# Sheet2.net
KiCad netlist of a schematic drawn in Altium Designer
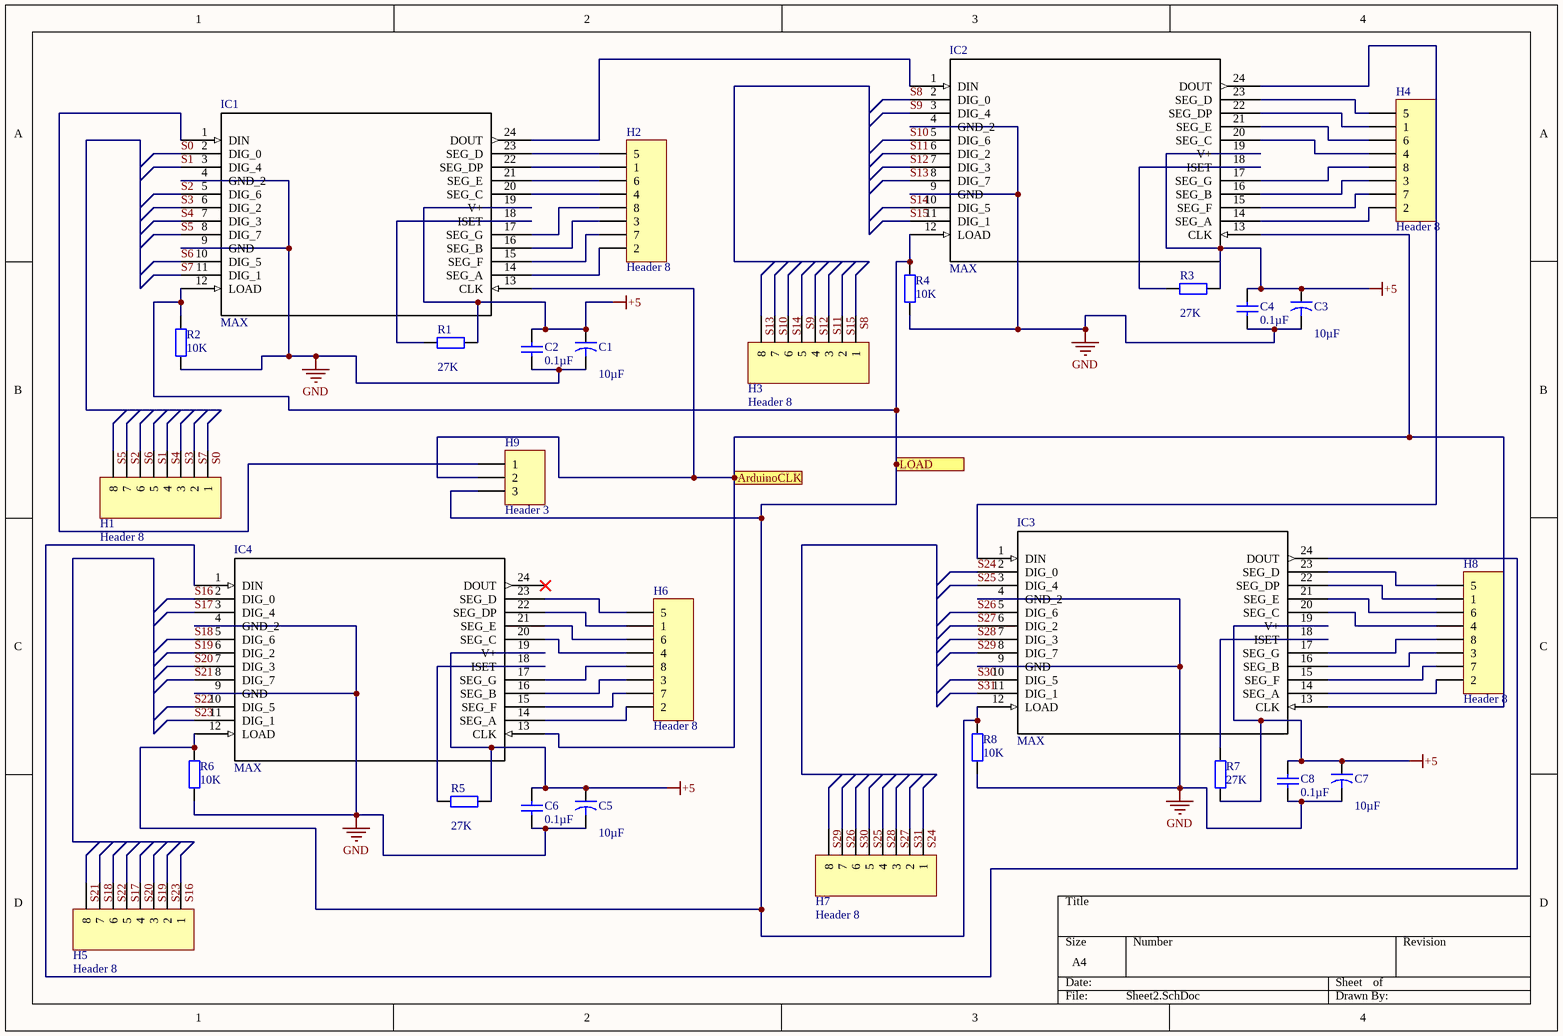
[diagram p0: Sheet2.SchDoc]

(export (version "E")
  (design (tool "Eeschema 10.0.6"))
  (components
    (comp (ref "C1")
      (value "10µF")
      (footprint "CAPR5-4X5")
      (description "Capacitor")
      (fields (field (name "Comment") "Cap2") (field (name "PUBLISHER") "Altium Limited"))
      (libsource (lib "Miscellaneous Devices") (part "Cap2"))
    )
    (comp (ref "C2")
      (value "0.1µF")
      (footprint "CAPC2013X94X50ML20T25")
      (description "Chip Capacitor, Ceramic, 0.1 uF, 10%, 50 V, 0805, RoHS, Tape and Reel")
      (fields (field (name "MANUFACTURER") "AVX"))
      (libsource (lib "Altium Content Vault") (part "CAP-NP-2"))
    )
    (comp (ref "C3")
      (value "10µF")
      (footprint "CAPR5-4X5")
      (description "Capacitor")
      (fields (field (name "Comment") "Cap2") (field (name "PUBLISHER") "Altium Limited"))
      (libsource (lib "Miscellaneous Devices") (part "Cap2"))
    )
    (comp (ref "C4")
      (value "0.1µF")
      (footprint "CAPC2013X94X50ML20T25")
      (description "Chip Capacitor, Ceramic, 0.1 uF, 10%, 50 V, 0805, RoHS, Tape and Reel")
      (fields (field (name "MANUFACTURER") "AVX"))
      (libsource (lib "Altium Content Vault") (part "CAP-NP-2"))
    )
    (comp (ref "C5")
      (value "10µF")
      (footprint "CAPR5-4X5")
      (description "Capacitor")
      (fields (field (name "Comment") "Cap2") (field (name "PUBLISHER") "Altium Limited"))
      (libsource (lib "Miscellaneous Devices") (part "Cap2"))
    )
    (comp (ref "C6")
      (value "0.1µF")
      (footprint "CAPC2013X94X50ML20T25")
      (description "Chip Capacitor, Ceramic, 0.1 uF, 10%, 50 V, 0805, RoHS, Tape and Reel")
      (fields (field (name "MANUFACTURER") "AVX"))
      (libsource (lib "Altium Content Vault") (part "CAP-NP-2"))
    )
    (comp (ref "C7")
      (value "10µF")
      (footprint "CAPR5-4X5")
      (description "Capacitor")
      (fields (field (name "Comment") "Cap2") (field (name "PUBLISHER") "Altium Limited"))
      (libsource (lib "Miscellaneous Devices") (part "Cap2"))
    )
    (comp (ref "C8")
      (value "0.1µF")
      (footprint "CAPC2013X94X50ML20T25")
      (description "Chip Capacitor, Ceramic, 0.1 uF, 10%, 50 V, 0805, RoHS, Tape and Reel")
      (fields (field (name "MANUFACTURER") "AVX"))
      (libsource (lib "Altium Content Vault") (part "CAP-NP-2"))
    )
    (comp (ref "H1")
      (value "Header 8")
      (footprint "HDR1X8")
      (description "Header, 8-Pin")
      (fields (field (name "PUBLISHER") "Altium Limited"))
      (libsource (lib "Miscellaneous Connectors") (part "Header 8"))
    )
    (comp (ref "H2")
      (value "Header 8")
      (footprint "HDR1X8")
      (description "Header, 8-Pin")
      (fields (field (name "PUBLISHER") "Altium Limited"))
      (libsource (lib "PCB_Project_1") (part "Header 8"))
    )
    (comp (ref "H3")
      (value "Header 8")
      (footprint "HDR1X8")
      (description "Header, 8-Pin")
      (fields (field (name "PUBLISHER") "Altium Limited"))
      (libsource (lib "Miscellaneous Connectors") (part "Header 8"))
    )
    (comp (ref "H4")
      (value "Header 8")
      (footprint "HDR1X8")
      (description "Header, 8-Pin")
      (fields (field (name "PUBLISHER") "Altium Limited"))
      (libsource (lib "PCB_Project_1") (part "Header 8"))
    )
    (comp (ref "H5")
      (value "Header 8")
      (footprint "HDR1X8")
      (description "Header, 8-Pin")
      (fields (field (name "PUBLISHER") "Altium Limited"))
      (libsource (lib "Miscellaneous Connectors") (part "Header 8"))
    )
    (comp (ref "H6")
      (value "Header 8")
      (footprint "HDR1X8")
      (description "Header, 8-Pin")
      (fields (field (name "PUBLISHER") "Altium Limited"))
      (libsource (lib "PCB_Project_1") (part "Header 8"))
    )
    (comp (ref "H7")
      (value "Header 8")
      (footprint "HDR1X8")
      (description "Header, 8-Pin")
      (fields (field (name "PUBLISHER") "Altium Limited"))
      (libsource (lib "Miscellaneous Connectors") (part "Header 8"))
    )
    (comp (ref "H8")
      (value "Header 8")
      (footprint "HDR1X8")
      (description "Header, 8-Pin")
      (fields (field (name "PUBLISHER") "Altium Limited"))
      (libsource (lib "PCB_Project_1") (part "Header 8"))
    )
    (comp (ref "H9")
      (value "Header 3")
      (footprint "HDR1X3")
      (description "Header, 3-Pin")
      (fields (field (name "PUBLISHER") "Altium Limited"))
      (libsource (lib "Miscellaneous Connectors") (part "Header 3"))
    )
    (comp (ref "IC1")
      (value "MAX")
      (footprint "MAX7219CWGT:*21-0042B_24")
      (libsource (lib "PCB_Project_1") (part "MAX"))
    )
    (comp (ref "IC2") (value "MAX") (footprint "*21-0042B_24") (libsource (lib "PCB_Project_1") (part "MAX")))
    (comp (ref "IC3") (value "MAX") (footprint "*21-0042B_24") (libsource (lib "PCB_Project_1") (part "MAX")))
    (comp (ref "IC4") (value "MAX") (footprint "*21-0042B_24") (libsource (lib "PCB_Project_1") (part "MAX")))
    (comp (ref "R1")
      (value "27K")
      (footprint "AXIAL-0.4")
      (description "Resistor")
      (fields (field (name "Comment") "Res2") (field (name "PUBLISHER") "Altium Limited"))
      (libsource (lib "") (part "Res2_1"))
    )
    (comp (ref "R2")
      (value "10K")
      (footprint "AXIAL-0.4")
      (description "Resistor")
      (fields (field (name "Comment") "Res2") (field (name "PUBLISHER") "Altium Limited"))
      (libsource (lib "Miscellaneous Devices") (part "Res2"))
    )
    (comp (ref "R3")
      (value "27K")
      (footprint "AXIAL-0.4")
      (description "Resistor")
      (fields (field (name "Comment") "Res2") (field (name "PUBLISHER") "Altium Limited"))
      (libsource (lib "") (part "Res2_1"))
    )
    (comp (ref "R4")
      (value "10K")
      (footprint "AXIAL-0.4")
      (description "Resistor")
      (fields (field (name "Comment") "Res2") (field (name "PUBLISHER") "Altium Limited"))
      (libsource (lib "Miscellaneous Devices") (part "Res2"))
    )
    (comp (ref "R5")
      (value "27K")
      (footprint "AXIAL-0.4")
      (description "Resistor")
      (fields (field (name "Comment") "Res2") (field (name "PUBLISHER") "Altium Limited"))
      (libsource (lib "") (part "Res2_1"))
    )
    (comp (ref "R6")
      (value "10K")
      (footprint "AXIAL-0.4")
      (description "Resistor")
      (fields (field (name "Comment") "Res2") (field (name "PUBLISHER") "Altium Limited"))
      (libsource (lib "Miscellaneous Devices") (part "Res2"))
    )
    (comp (ref "R7")
      (value "27K")
      (footprint "AXIAL-0.4")
      (description "Resistor")
      (fields (field (name "Comment") "Res2") (field (name "PUBLISHER") "Altium Limited"))
      (libsource (lib "Miscellaneous Devices") (part "Res2"))
    )
    (comp (ref "R8")
      (value "10K")
      (footprint "AXIAL-0.4")
      (description "Resistor")
      (fields (field (name "Comment") "Res2") (field (name "PUBLISHER") "Altium Limited"))
      (libsource (lib "Miscellaneous Devices") (part "Res2"))
    )
  )
  (nets
    (net (code "1") (name "+5") (class "Default")
      (node (ref "C1") (pin "1") (pinfunction "1_1") (pintype "passive"))
      (node (ref "C2") (pin "1") (pinfunction "1_1") (pintype "passive"))
      (node (ref "C3") (pin "1") (pinfunction "1_1") (pintype "passive"))
      (node (ref "C4") (pin "2") (pinfunction "2_2") (pintype "passive"))
      (node (ref "C5") (pin "1") (pinfunction "1_1") (pintype "passive"))
      (node (ref "C6") (pin "2") (pinfunction "2_2") (pintype "passive"))
      (node (ref "C7") (pin "1") (pinfunction "1_1") (pintype "passive"))
      (node (ref "C8") (pin "2") (pinfunction "2_2") (pintype "passive"))
      (node (ref "IC1") (pin "19") (pinfunction "V+_19") (pintype "power_in"))
      (node (ref "IC2") (pin "19") (pinfunction "V+_19") (pintype "power_in"))
      (node (ref "IC3") (pin "19") (pinfunction "V+_19") (pintype "power_in"))
      (node (ref "IC4") (pin "19") (pinfunction "V+_19") (pintype "power_in"))
      (node (ref "R1") (pin "2") (pinfunction "2_2") (pintype "passive"))
      (node (ref "R3") (pin "2") (pinfunction "2_2") (pintype "passive"))
      (node (ref "R5") (pin "2") (pinfunction "2_2") (pintype "passive"))
      (node (ref "R7") (pin "1") (pinfunction "1_1") (pintype "passive"))
    )
    (net (code "2") (name "/ArduinoCLK") (class "Default")
      (node (ref "H9") (pin "2") (pinfunction "2_2") (pintype "passive"))
      (node (ref "IC1") (pin "13") (pinfunction "CLK_13") (pintype "input"))
      (node (ref "IC2") (pin "13") (pinfunction "CLK_13") (pintype "input"))
      (node (ref "IC3") (pin "13") (pinfunction "CLK_13") (pintype "input"))
      (node (ref "IC4") (pin "13") (pinfunction "CLK_13") (pintype "input"))
    )
    (net (code "3") (name "/LOAD") (class "Default")
      (node (ref "H9") (pin "3") (pinfunction "3_3") (pintype "passive"))
      (node (ref "IC1") (pin "12") (pinfunction "LOAD_12") (pintype "input"))
      (node (ref "IC2") (pin "12") (pinfunction "LOAD_12") (pintype "input"))
      (node (ref "IC3") (pin "12") (pinfunction "LOAD_12") (pintype "input"))
      (node (ref "IC4") (pin "12") (pinfunction "LOAD_12") (pintype "input"))
      (node (ref "R2") (pin "2") (pinfunction "2_2") (pintype "passive"))
      (node (ref "R4") (pin "2") (pinfunction "2_2") (pintype "passive"))
      (node (ref "R6") (pin "2") (pinfunction "2_2") (pintype "passive"))
      (node (ref "R8") (pin "2") (pinfunction "2_2") (pintype "passive"))
    )
    (net (code "4") (name "/S0") (class "Default")
      (node (ref "H1") (pin "1") (pinfunction "1_1") (pintype "passive"))
      (node (ref "IC1") (pin "2") (pinfunction "DIG_0_2") (pintype "passive"))
    )
    (net (code "5") (name "/S1") (class "Default")
      (node (ref "H1") (pin "5") (pinfunction "5_5") (pintype "passive"))
      (node (ref "IC1") (pin "3") (pinfunction "DIG_4_3") (pintype "passive"))
    )
    (net (code "6") (name "/S2") (class "Default")
      (node (ref "H1") (pin "7") (pinfunction "7_7") (pintype "passive"))
      (node (ref "IC1") (pin "5") (pinfunction "DIG_6_5") (pintype "passive"))
    )
    (net (code "7") (name "/S3") (class "Default")
      (node (ref "H1") (pin "3") (pinfunction "3_3") (pintype "passive"))
      (node (ref "IC1") (pin "6") (pinfunction "DIG_2_6") (pintype "passive"))
    )
    (net (code "8") (name "/S4") (class "Default")
      (node (ref "H1") (pin "4") (pinfunction "4_4") (pintype "passive"))
      (node (ref "IC1") (pin "7") (pinfunction "DIG_3_7") (pintype "passive"))
    )
    (net (code "9") (name "/S5") (class "Default")
      (node (ref "H1") (pin "8") (pinfunction "8_8") (pintype "passive"))
      (node (ref "IC1") (pin "8") (pinfunction "DIG_7_8") (pintype "passive"))
    )
    (net (code "10") (name "/S6") (class "Default")
      (node (ref "H1") (pin "6") (pinfunction "6_6") (pintype "passive"))
      (node (ref "IC1") (pin "10") (pinfunction "DIG_5_10") (pintype "passive"))
    )
    (net (code "11") (name "/S7") (class "Default")
      (node (ref "H1") (pin "2") (pinfunction "2_2") (pintype "passive"))
      (node (ref "IC1") (pin "11") (pinfunction "DIG_1_11") (pintype "passive"))
    )
    (net (code "12") (name "/S8") (class "Default")
      (node (ref "H3") (pin "1") (pinfunction "1_1") (pintype "passive"))
      (node (ref "IC2") (pin "2") (pinfunction "DIG_0_2") (pintype "passive"))
    )
    (net (code "13") (name "/S9") (class "Default")
      (node (ref "H3") (pin "5") (pinfunction "5_5") (pintype "passive"))
      (node (ref "IC2") (pin "3") (pinfunction "DIG_4_3") (pintype "passive"))
    )
    (net (code "14") (name "/S10") (class "Default")
      (node (ref "H3") (pin "7") (pinfunction "7_7") (pintype "passive"))
      (node (ref "IC2") (pin "5") (pinfunction "DIG_6_5") (pintype "passive"))
    )
    (net (code "15") (name "/S11") (class "Default")
      (node (ref "H3") (pin "3") (pinfunction "3_3") (pintype "passive"))
      (node (ref "IC2") (pin "6") (pinfunction "DIG_2_6") (pintype "passive"))
    )
    (net (code "16") (name "/S12") (class "Default")
      (node (ref "H3") (pin "4") (pinfunction "4_4") (pintype "passive"))
      (node (ref "IC2") (pin "7") (pinfunction "DIG_3_7") (pintype "passive"))
    )
    (net (code "17") (name "/S13") (class "Default")
      (node (ref "H3") (pin "8") (pinfunction "8_8") (pintype "passive"))
      (node (ref "IC2") (pin "8") (pinfunction "DIG_7_8") (pintype "passive"))
    )
    (net (code "18") (name "/S14") (class "Default")
      (node (ref "H3") (pin "6") (pinfunction "6_6") (pintype "passive"))
      (node (ref "IC2") (pin "10") (pinfunction "DIG_5_10") (pintype "passive"))
    )
    (net (code "19") (name "/S15") (class "Default")
      (node (ref "H3") (pin "2") (pinfunction "2_2") (pintype "passive"))
      (node (ref "IC2") (pin "11") (pinfunction "DIG_1_11") (pintype "passive"))
    )
    (net (code "20") (name "/S16") (class "Default")
      (node (ref "H5") (pin "1") (pinfunction "1_1") (pintype "passive"))
      (node (ref "IC4") (pin "2") (pinfunction "DIG_0_2") (pintype "passive"))
    )
    (net (code "21") (name "/S17") (class "Default")
      (node (ref "H5") (pin "5") (pinfunction "5_5") (pintype "passive"))
      (node (ref "IC4") (pin "3") (pinfunction "DIG_4_3") (pintype "passive"))
    )
    (net (code "22") (name "/S18") (class "Default")
      (node (ref "H5") (pin "7") (pinfunction "7_7") (pintype "passive"))
      (node (ref "IC4") (pin "5") (pinfunction "DIG_6_5") (pintype "passive"))
    )
    (net (code "23") (name "/S19") (class "Default")
      (node (ref "H5") (pin "3") (pinfunction "3_3") (pintype "passive"))
      (node (ref "IC4") (pin "6") (pinfunction "DIG_2_6") (pintype "passive"))
    )
    (net (code "24") (name "/S20") (class "Default")
      (node (ref "H5") (pin "4") (pinfunction "4_4") (pintype "passive"))
      (node (ref "IC4") (pin "7") (pinfunction "DIG_3_7") (pintype "passive"))
    )
    (net (code "25") (name "/S21") (class "Default")
      (node (ref "H5") (pin "8") (pinfunction "8_8") (pintype "passive"))
      (node (ref "IC4") (pin "8") (pinfunction "DIG_7_8") (pintype "passive"))
    )
    (net (code "26") (name "/S22") (class "Default")
      (node (ref "H5") (pin "6") (pinfunction "6_6") (pintype "passive"))
      (node (ref "IC4") (pin "10") (pinfunction "DIG_5_10") (pintype "passive"))
    )
    (net (code "27") (name "/S23") (class "Default")
      (node (ref "H5") (pin "2") (pinfunction "2_2") (pintype "passive"))
      (node (ref "IC4") (pin "11") (pinfunction "DIG_1_11") (pintype "passive"))
    )
    (net (code "28") (name "/S24") (class "Default")
      (node (ref "H7") (pin "1") (pinfunction "1_1") (pintype "passive"))
      (node (ref "IC3") (pin "2") (pinfunction "DIG_0_2") (pintype "passive"))
    )
    (net (code "29") (name "/S25") (class "Default")
      (node (ref "H7") (pin "5") (pinfunction "5_5") (pintype "passive"))
      (node (ref "IC3") (pin "3") (pinfunction "DIG_4_3") (pintype "passive"))
    )
    (net (code "30") (name "/S26") (class "Default")
      (node (ref "H7") (pin "7") (pinfunction "7_7") (pintype "passive"))
      (node (ref "IC3") (pin "5") (pinfunction "DIG_6_5") (pintype "passive"))
    )
    (net (code "31") (name "/S27") (class "Default")
      (node (ref "H7") (pin "3") (pinfunction "3_3") (pintype "passive"))
      (node (ref "IC3") (pin "6") (pinfunction "DIG_2_6") (pintype "passive"))
    )
    (net (code "32") (name "/S28") (class "Default")
      (node (ref "H7") (pin "4") (pinfunction "4_4") (pintype "passive"))
      (node (ref "IC3") (pin "7") (pinfunction "DIG_3_7") (pintype "passive"))
    )
    (net (code "33") (name "/S29") (class "Default")
      (node (ref "H7") (pin "8") (pinfunction "8_8") (pintype "passive"))
      (node (ref "IC3") (pin "8") (pinfunction "DIG_7_8") (pintype "passive"))
    )
    (net (code "34") (name "/S30") (class "Default")
      (node (ref "H7") (pin "6") (pinfunction "6_6") (pintype "passive"))
      (node (ref "IC3") (pin "10") (pinfunction "DIG_5_10") (pintype "passive"))
    )
    (net (code "35") (name "/S31") (class "Default")
      (node (ref "H7") (pin "2") (pinfunction "2_2") (pintype "passive"))
      (node (ref "IC3") (pin "11") (pinfunction "DIG_1_11") (pintype "passive"))
    )
    (net (code "36") (name "GND") (class "Default")
      (node (ref "C1") (pin "2") (pinfunction "2_2") (pintype "passive"))
      (node (ref "C2") (pin "2") (pinfunction "2_2") (pintype "passive"))
      (node (ref "C3") (pin "2") (pinfunction "2_2") (pintype "passive"))
      (node (ref "C4") (pin "1") (pinfunction "1_1") (pintype "passive"))
      (node (ref "C5") (pin "2") (pinfunction "2_2") (pintype "passive"))
      (node (ref "C6") (pin "1") (pinfunction "1_1") (pintype "passive"))
      (node (ref "C7") (pin "2") (pinfunction "2_2") (pintype "passive"))
      (node (ref "C8") (pin "1") (pinfunction "1_1") (pintype "passive"))
      (node (ref "IC1") (pin "4") (pinfunction "GND_2_4") (pintype "power_in"))
      (node (ref "IC1") (pin "9") (pinfunction "GND_9") (pintype "power_in"))
      (node (ref "IC2") (pin "4") (pinfunction "GND_2_4") (pintype "power_in"))
      (node (ref "IC2") (pin "9") (pinfunction "GND_9") (pintype "power_in"))
      (node (ref "IC3") (pin "4") (pinfunction "GND_2_4") (pintype "power_in"))
      (node (ref "IC3") (pin "9") (pinfunction "GND_9") (pintype "power_in"))
      (node (ref "IC4") (pin "4") (pinfunction "GND_2_4") (pintype "power_in"))
      (node (ref "IC4") (pin "9") (pinfunction "GND_9") (pintype "power_in"))
      (node (ref "R2") (pin "1") (pinfunction "1_1") (pintype "passive"))
      (node (ref "R4") (pin "1") (pinfunction "1_1") (pintype "passive"))
      (node (ref "R6") (pin "1") (pinfunction "1_1") (pintype "passive"))
      (node (ref "R8") (pin "1") (pinfunction "1_1") (pintype "passive"))
    )
    (net (code "37") (name "Net-(H2-1)") (class "Default")
      (node (ref "H2") (pin "2") (pinfunction "1_2") (pintype "passive"))
      (node (ref "IC1") (pin "22") (pinfunction "SEG_DP_22") (pintype "passive"))
    )
    (net (code "38") (name "Net-(H2-2)") (class "Default")
      (node (ref "H2") (pin "8") (pinfunction "2_8") (pintype "passive"))
      (node (ref "IC1") (pin "14") (pinfunction "SEG_A_14") (pintype "passive"))
    )
    (net (code "39") (name "Net-(H2-3)") (class "Default")
      (node (ref "H2") (pin "6") (pinfunction "3_6") (pintype "passive"))
      (node (ref "IC1") (pin "16") (pinfunction "SEG_B_16") (pintype "passive"))
    )
    (net (code "40") (name "Net-(H2-5)") (class "Default")
      (node (ref "H2") (pin "1") (pinfunction "5_1") (pintype "passive"))
      (node (ref "IC1") (pin "23") (pinfunction "SEG_D_23") (pintype "passive"))
    )
    (net (code "41") (name "Net-(H2-6)") (class "Default")
      (node (ref "H2") (pin "3") (pinfunction "6_3") (pintype "passive"))
      (node (ref "IC1") (pin "21") (pinfunction "SEG_E_21") (pintype "passive"))
    )
    (net (code "42") (name "Net-(H2-8)") (class "Default")
      (node (ref "H2") (pin "5") (pinfunction "8_5") (pintype "passive"))
      (node (ref "IC1") (pin "17") (pinfunction "SEG_G_17") (pintype "passive"))
    )
    (net (code "43") (name "Net-(H4-1)") (class "Default")
      (node (ref "H4") (pin "2") (pinfunction "1_2") (pintype "passive"))
      (node (ref "IC2") (pin "22") (pinfunction "SEG_DP_22") (pintype "passive"))
    )
    (net (code "44") (name "Net-(H4-2)") (class "Default")
      (node (ref "H4") (pin "8") (pinfunction "2_8") (pintype "passive"))
      (node (ref "IC2") (pin "14") (pinfunction "SEG_A_14") (pintype "passive"))
    )
    (net (code "45") (name "Net-(H4-3)") (class "Default")
      (node (ref "H4") (pin "6") (pinfunction "3_6") (pintype "passive"))
      (node (ref "IC2") (pin "16") (pinfunction "SEG_B_16") (pintype "passive"))
    )
    (net (code "46") (name "Net-(H4-5)") (class "Default")
      (node (ref "H4") (pin "1") (pinfunction "5_1") (pintype "passive"))
      (node (ref "IC2") (pin "23") (pinfunction "SEG_D_23") (pintype "passive"))
    )
    (net (code "47") (name "Net-(H4-6)") (class "Default")
      (node (ref "H4") (pin "3") (pinfunction "6_3") (pintype "passive"))
      (node (ref "IC2") (pin "21") (pinfunction "SEG_E_21") (pintype "passive"))
    )
    (net (code "48") (name "Net-(H4-8)") (class "Default")
      (node (ref "H4") (pin "5") (pinfunction "8_5") (pintype "passive"))
      (node (ref "IC2") (pin "17") (pinfunction "SEG_G_17") (pintype "passive"))
    )
    (net (code "49") (name "Net-(H6-1)") (class "Default")
      (node (ref "H6") (pin "2") (pinfunction "1_2") (pintype "passive"))
      (node (ref "IC4") (pin "22") (pinfunction "SEG_DP_22") (pintype "passive"))
    )
    (net (code "50") (name "Net-(H6-2)") (class "Default")
      (node (ref "H6") (pin "8") (pinfunction "2_8") (pintype "passive"))
      (node (ref "IC4") (pin "14") (pinfunction "SEG_A_14") (pintype "passive"))
    )
    (net (code "51") (name "Net-(H6-3)") (class "Default")
      (node (ref "H6") (pin "6") (pinfunction "3_6") (pintype "passive"))
      (node (ref "IC4") (pin "16") (pinfunction "SEG_B_16") (pintype "passive"))
    )
    (net (code "52") (name "Net-(H6-5)") (class "Default")
      (node (ref "H6") (pin "1") (pinfunction "5_1") (pintype "passive"))
      (node (ref "IC4") (pin "23") (pinfunction "SEG_D_23") (pintype "passive"))
    )
    (net (code "53") (name "Net-(H6-6)") (class "Default")
      (node (ref "H6") (pin "3") (pinfunction "6_3") (pintype "passive"))
      (node (ref "IC4") (pin "21") (pinfunction "SEG_E_21") (pintype "passive"))
    )
    (net (code "54") (name "Net-(H6-8)") (class "Default")
      (node (ref "H6") (pin "5") (pinfunction "8_5") (pintype "passive"))
      (node (ref "IC4") (pin "17") (pinfunction "SEG_G_17") (pintype "passive"))
    )
    (net (code "55") (name "Net-(H8-1)") (class "Default")
      (node (ref "H8") (pin "2") (pinfunction "1_2") (pintype "passive"))
      (node (ref "IC3") (pin "22") (pinfunction "SEG_DP_22") (pintype "passive"))
    )
    (net (code "56") (name "Net-(H8-2)") (class "Default")
      (node (ref "H8") (pin "8") (pinfunction "2_8") (pintype "passive"))
      (node (ref "IC3") (pin "14") (pinfunction "SEG_A_14") (pintype "passive"))
    )
    (net (code "57") (name "Net-(H8-3)") (class "Default")
      (node (ref "H8") (pin "6") (pinfunction "3_6") (pintype "passive"))
      (node (ref "IC3") (pin "16") (pinfunction "SEG_B_16") (pintype "passive"))
    )
    (net (code "58") (name "Net-(H8-5)") (class "Default")
      (node (ref "H8") (pin "1") (pinfunction "5_1") (pintype "passive"))
      (node (ref "IC3") (pin "23") (pinfunction "SEG_D_23") (pintype "passive"))
    )
    (net (code "59") (name "Net-(H8-6)") (class "Default")
      (node (ref "H8") (pin "3") (pinfunction "6_3") (pintype "passive"))
      (node (ref "IC3") (pin "21") (pinfunction "SEG_E_21") (pintype "passive"))
    )
    (net (code "60") (name "Net-(H8-8)") (class "Default")
      (node (ref "H8") (pin "5") (pinfunction "8_5") (pintype "passive"))
      (node (ref "IC3") (pin "17") (pinfunction "SEG_G_17") (pintype "passive"))
    )
    (net (code "61") (name "Net-(IC1-DIN)") (class "Default")
      (node (ref "H9") (pin "1") (pinfunction "1_1") (pintype "passive"))
      (node (ref "IC1") (pin "1") (pinfunction "DIN_1") (pintype "input"))
    )
    (net (code "62") (name "Net-(IC1-DOUT)") (class "Default")
      (node (ref "IC1") (pin "24") (pinfunction "DOUT_24") (pintype "output"))
      (node (ref "IC2") (pin "1") (pinfunction "DIN_1") (pintype "input"))
    )
    (net (code "63") (name "Net-(IC1-ISET)") (class "Default")
      (node (ref "IC1") (pin "18") (pinfunction "ISET_18") (pintype "passive"))
      (node (ref "R1") (pin "1") (pinfunction "1_1") (pintype "passive"))
    )
    (net (code "64") (name "Net-(IC1-SEG_C)") (class "Default")
      (node (ref "H2") (pin "4") (pinfunction "4_4") (pintype "passive"))
      (node (ref "IC1") (pin "20") (pinfunction "SEG_C_20") (pintype "passive"))
    )
    (net (code "65") (name "Net-(IC1-SEG_F)") (class "Default")
      (node (ref "H2") (pin "7") (pinfunction "7_7") (pintype "passive"))
      (node (ref "IC1") (pin "15") (pinfunction "SEG_F_15") (pintype "passive"))
    )
    (net (code "66") (name "Net-(IC2-DOUT)") (class "Default")
      (node (ref "IC2") (pin "24") (pinfunction "DOUT_24") (pintype "output"))
      (node (ref "IC3") (pin "1") (pinfunction "DIN_1") (pintype "input"))
    )
    (net (code "67") (name "Net-(IC2-ISET)") (class "Default")
      (node (ref "IC2") (pin "18") (pinfunction "ISET_18") (pintype "passive"))
      (node (ref "R3") (pin "1") (pinfunction "1_1") (pintype "passive"))
    )
    (net (code "68") (name "Net-(IC2-SEG_C)") (class "Default")
      (node (ref "H4") (pin "4") (pinfunction "4_4") (pintype "passive"))
      (node (ref "IC2") (pin "20") (pinfunction "SEG_C_20") (pintype "passive"))
    )
    (net (code "69") (name "Net-(IC2-SEG_F)") (class "Default")
      (node (ref "H4") (pin "7") (pinfunction "7_7") (pintype "passive"))
      (node (ref "IC2") (pin "15") (pinfunction "SEG_F_15") (pintype "passive"))
    )
    (net (code "70") (name "Net-(IC3-DOUT)") (class "Default")
      (node (ref "IC3") (pin "24") (pinfunction "DOUT_24") (pintype "output"))
      (node (ref "IC4") (pin "1") (pinfunction "DIN_1") (pintype "input"))
    )
    (net (code "71") (name "Net-(IC3-ISET)") (class "Default")
      (node (ref "IC3") (pin "18") (pinfunction "ISET_18") (pintype "passive"))
      (node (ref "R7") (pin "2") (pinfunction "2_2") (pintype "passive"))
    )
    (net (code "72") (name "Net-(IC3-SEG_C)") (class "Default")
      (node (ref "H8") (pin "4") (pinfunction "4_4") (pintype "passive"))
      (node (ref "IC3") (pin "20") (pinfunction "SEG_C_20") (pintype "passive"))
    )
    (net (code "73") (name "Net-(IC3-SEG_F)") (class "Default")
      (node (ref "H8") (pin "7") (pinfunction "7_7") (pintype "passive"))
      (node (ref "IC3") (pin "15") (pinfunction "SEG_F_15") (pintype "passive"))
    )
    (net (code "74") (name "Net-(IC4-ISET)") (class "Default")
      (node (ref "IC4") (pin "18") (pinfunction "ISET_18") (pintype "passive"))
      (node (ref "R5") (pin "1") (pinfunction "1_1") (pintype "passive"))
    )
    (net (code "75") (name "Net-(IC4-SEG_C)") (class "Default")
      (node (ref "H6") (pin "4") (pinfunction "4_4") (pintype "passive"))
      (node (ref "IC4") (pin "20") (pinfunction "SEG_C_20") (pintype "passive"))
    )
    (net (code "76") (name "Net-(IC4-SEG_F)") (class "Default")
      (node (ref "H6") (pin "7") (pinfunction "7_7") (pintype "passive"))
      (node (ref "IC4") (pin "15") (pinfunction "SEG_F_15") (pintype "passive"))
    )
    (net (code "77") (name "unconnected-(IC4-DOUT-Pad24)") (class "Default")
      (node (ref "IC4") (pin "24") (pinfunction "DOUT_24") (pintype "output+no_connect"))
    )
  )
)
